# WL-CONTROL.net
KiCad netlist of a schematic drawn in Altium Designer
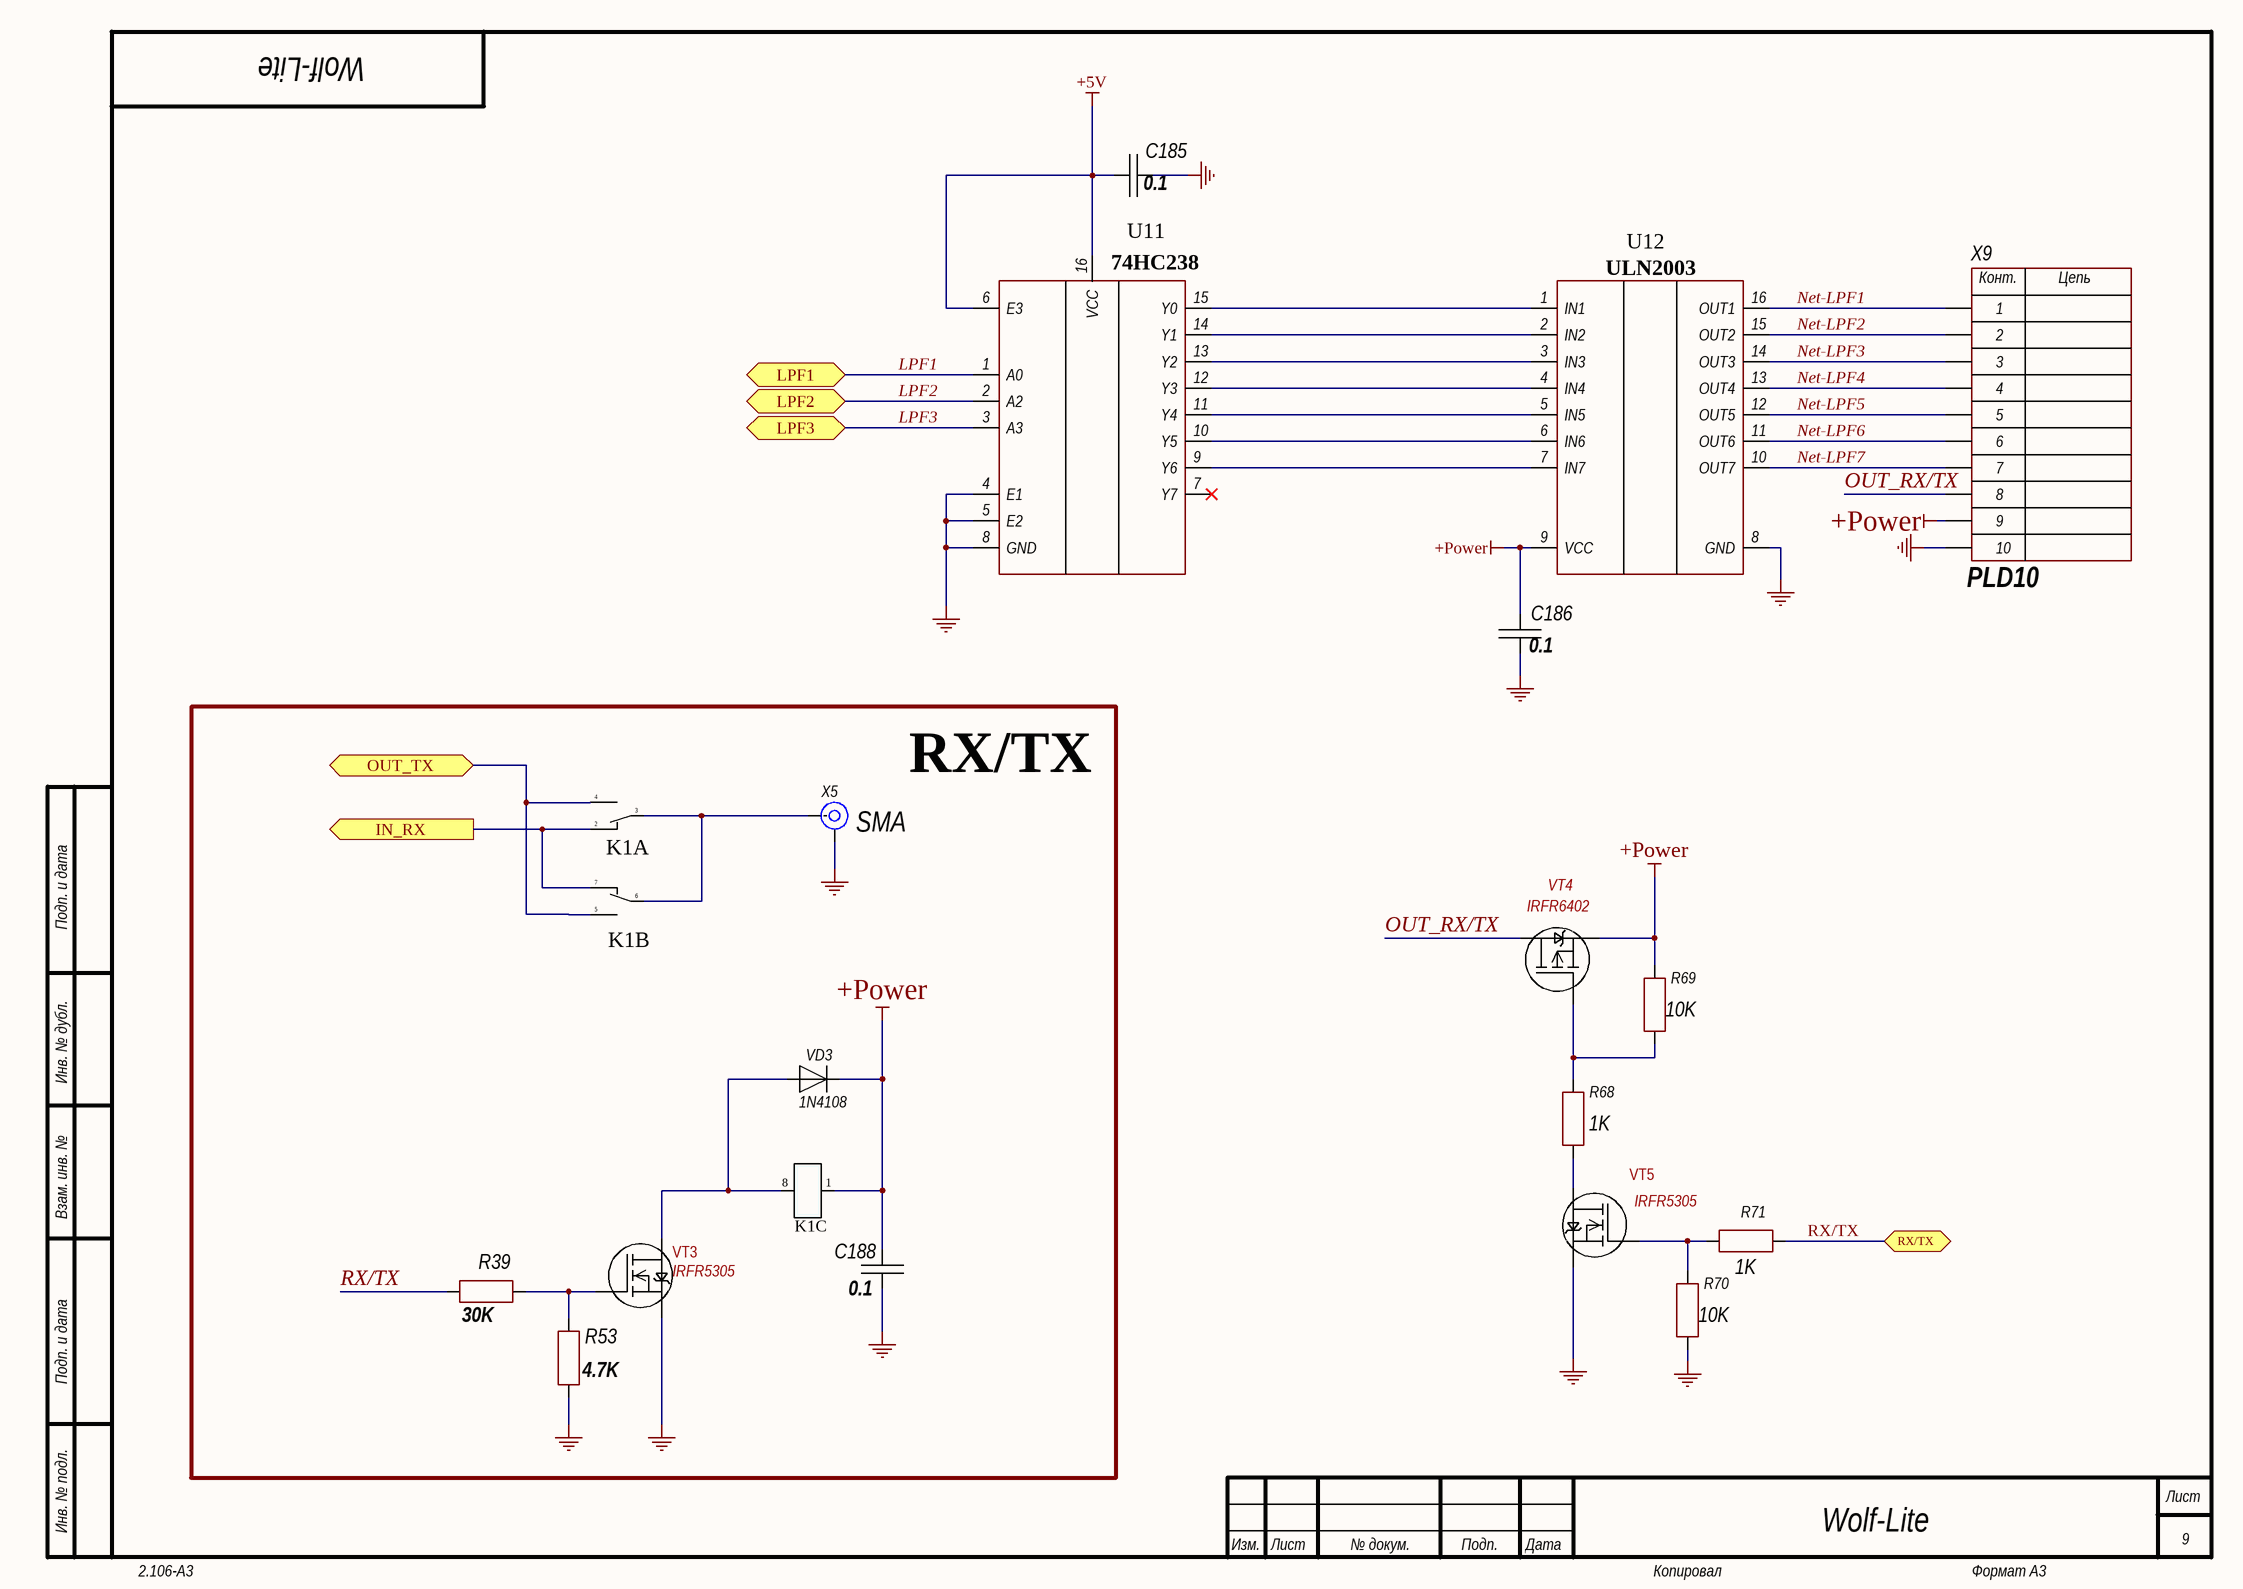
[diagram p0: WL-CONTROL.SchDoc]

(export (version "E")
  (design (tool "Eeschema 10.0.6"))
  (components
    (comp (ref "C185")
      (value "0.1")
      (footprint "standard:CH0805C")
      (libsource (lib "Discrete") (part "Capacitor"))
    )
    (comp (ref "C186")
      (value "0.1")
      (footprint "standard:CH0805C")
      (libsource (lib "Discrete") (part "Capacitor"))
    )
    (comp (ref "C188")
      (value "0.1")
      (footprint "standard:CH0805C")
      (libsource (lib "Discrete") (part "Capacitor"))
    )
    (comp (ref "K1") (value "IM06") (footprint "IMG06") (libsource (lib "Relay") (part "IM06-1")))
    (comp (ref "R39") (value "30K") (footprint "standard:CH0805R") (libsource (lib "") (part "Resistor_1")))
    (comp (ref "R53")
      (value "4.7K")
      (footprint "standard:CH0805R")
      (libsource (lib "Discrete") (part "Resistor"))
    )
    (comp (ref "R68")
      (value "1K")
      (footprint "standard:CH0805R")
      (libsource (lib "Discrete") (part "Resistor"))
    )
    (comp (ref "R69")
      (value "10K")
      (footprint "standard:CH0805R")
      (libsource (lib "Discrete") (part "Resistor"))
    )
    (comp (ref "R70")
      (value "10K")
      (footprint "standard:CH0805R")
      (libsource (lib "Discrete") (part "Resistor"))
    )
    (comp (ref "R71") (value "1K") (footprint "standard:CH0805R") (libsource (lib "") (part "Resistor_1")))
    (comp (ref "U11") (value "74HC238") (footprint "16-SOIC") (libsource (lib "Digital") (part "74HC238")))
    (comp (ref "U12")
      (value "ULN2003")
      (footprint "16-SOIC")
      (libsource (lib "Digital") (part "ULN2003_NEW"))
    )
    (comp (ref "VD3") (value "1N4108") (footprint "1N4148") (libsource (lib "Diods") (part "Diod")))
    (comp (ref "VT3") (value "IRFR5305") (footprint "SOT23_132") (libsource (lib "") (part "N-KANAL_1")))
    (comp (ref "VT4")
      (value "IRFR6402")
      (footprint "SOT23_132")
      (libsource (lib "Transistor") (part "P-KANAL"))
    )
    (comp (ref "VT5")
      (value "IRFR5305")
      (footprint "SOT23_132")
      (libsource (lib "Transistor") (part "N-KANAL"))
    )
    (comp (ref "X5")
      (value "SMA")
      (footprint "custom:CON: SMA")
      (description "RF")
      (libsource (lib "Connectors") (part "SMA"))
    )
    (comp (ref "X9")
      (value "PLD10")
      (footprint "custom:CON: PLD-10")
      (libsource (lib "Connectors") (part "10-Connector"))
    )
  )
  (nets
    (net (code "1") (name "+5V") (class "Default")
      (node (ref "C185") (pin "1") (pinfunction "1_1") (pintype "power_in"))
      (node (ref "U11") (pin "16") (pinfunction "VCC_16") (pintype "passive"))
      (node (ref "U11") (pin "6") (pinfunction "E3_6") (pintype "passive"))
    )
    (net (code "2") (name "+Power") (class "Default")
      (node (ref "C186") (pin "2") (pinfunction "2_2") (pintype "power_in"))
      (node (ref "C188") (pin "1") (pinfunction "1_1") (pintype "power_in"))
      (node (ref "K1") (pin "1") (pintype "passive"))
      (node (ref "R69") (pin "2") (pinfunction "2_2") (pintype "passive"))
      (node (ref "U12") (pin "9") (pinfunction "VCC_9") (pintype "passive"))
      (node (ref "VD3") (pin "2") (pinfunction "2_2") (pintype "passive"))
      (node (ref "VT4") (pin "2") (pinfunction "I_2") (pintype "passive"))
      (node (ref "X9") (pin "9") (pinfunction "9_9") (pintype "power_in"))
    )
    (net (code "3") (name "/IN_RX") (class "Default")
      (node (ref "K1") (pin "2") (pintype "passive"))
      (node (ref "K1") (pin "7") (pintype "passive"))
    )
    (net (code "4") (name "/LPF1") (class "Default")
      (node (ref "U11") (pin "1") (pinfunction "A0_1") (pintype "passive"))
    )
    (net (code "5") (name "/LPF2") (class "Default")
      (node (ref "U11") (pin "2") (pinfunction "A2_2") (pintype "passive"))
    )
    (net (code "6") (name "/LPF3") (class "Default")
      (node (ref "U11") (pin "3") (pinfunction "A3_3") (pintype "passive"))
    )
    (net (code "7") (name "/Net-LPF1") (class "Default")
      (node (ref "U12") (pin "16") (pinfunction "OUT1_16") (pintype "passive"))
      (node (ref "X9") (pin "1") (pinfunction "1_1") (pintype "passive"))
    )
    (net (code "8") (name "/Net-LPF2") (class "Default")
      (node (ref "U12") (pin "15") (pinfunction "OUT2_15") (pintype "passive"))
      (node (ref "X9") (pin "2") (pinfunction "2_2") (pintype "passive"))
    )
    (net (code "9") (name "/Net-LPF3") (class "Default")
      (node (ref "U12") (pin "14") (pinfunction "OUT3_14") (pintype "passive"))
      (node (ref "X9") (pin "3") (pinfunction "3_3") (pintype "power_in"))
    )
    (net (code "10") (name "/Net-LPF4") (class "Default")
      (node (ref "U12") (pin "13") (pinfunction "OUT4_13") (pintype "passive"))
      (node (ref "X9") (pin "4") (pinfunction "4_4") (pintype "power_in"))
    )
    (net (code "11") (name "/Net-LPF5") (class "Default")
      (node (ref "U12") (pin "12") (pinfunction "OUT5_12") (pintype "passive"))
      (node (ref "X9") (pin "5") (pinfunction "5_5") (pintype "power_in"))
    )
    (net (code "12") (name "/Net-LPF6") (class "Default")
      (node (ref "U12") (pin "11") (pinfunction "OUT6_11") (pintype "passive"))
      (node (ref "X9") (pin "6") (pinfunction "6_6") (pintype "power_in"))
    )
    (net (code "13") (name "/Net-LPF7") (class "Default")
      (node (ref "U12") (pin "10") (pinfunction "OUT7_10") (pintype "passive"))
      (node (ref "X9") (pin "7") (pinfunction "7_7") (pintype "power_in"))
    )
    (net (code "14") (name "/OUT_RX{slash}TX") (class "Default")
      (node (ref "VT4") (pin "3") (pinfunction "Сток(Drain)_3") (pintype "passive"))
      (node (ref "X9") (pin "8") (pinfunction "8_8") (pintype "power_in"))
    )
    (net (code "15") (name "/OUT_TX") (class "Default")
      (node (ref "K1") (pin "4") (pintype "passive"))
      (node (ref "K1") (pin "5") (pintype "passive"))
    )
    (net (code "16") (name "/RX{slash}TX") (class "Default")
      (node (ref "R39") (pin "2") (pinfunction "2_2") (pintype "passive"))
      (node (ref "R71") (pin "1") (pinfunction "1_1") (pintype "passive"))
    )
    (net (code "17") (name "GND") (class "Default")
      (node (ref "C185") (pin "2") (pinfunction "2_2") (pintype "power_in"))
      (node (ref "C186") (pin "1") (pinfunction "1_1") (pintype "power_in"))
      (node (ref "C188") (pin "2") (pinfunction "2_2") (pintype "power_in"))
      (node (ref "R53") (pin "1") (pinfunction "1_1") (pintype "passive"))
      (node (ref "R70") (pin "1") (pinfunction "1_1") (pintype "passive"))
      (node (ref "U11") (pin "4") (pinfunction "E1_4") (pintype "passive"))
      (node (ref "U11") (pin "5") (pinfunction "E2_5") (pintype "passive"))
      (node (ref "U11") (pin "8") (pinfunction "GND_8") (pintype "passive"))
      (node (ref "U12") (pin "8") (pinfunction "GND_8") (pintype "passive"))
      (node (ref "VT3") (pin "2") (pinfunction "I_2") (pintype "passive"))
      (node (ref "VT5") (pin "2") (pinfunction "I_2") (pintype "passive"))
      (node (ref "X5") (pin "2") (pinfunction "IN_2") (pintype "passive"))
      (node (ref "X9") (pin "10") (pinfunction "10_10") (pintype "power_in"))
    )
    (net (code "18") (name "Net-(K1-Pad3)") (class "Default")
      (node (ref "K1") (pin "3") (pintype "passive"))
      (node (ref "K1") (pin "6") (pintype "passive"))
      (node (ref "X5") (pin "1") (pinfunction "IN_1") (pintype "passive"))
    )
    (net (code "19") (name "Net-(U11-Y0)") (class "Default")
      (node (ref "U11") (pin "15") (pinfunction "Y0_15") (pintype "passive"))
      (node (ref "U12") (pin "1") (pinfunction "IN1_1") (pintype "passive"))
    )
    (net (code "20") (name "Net-(U11-Y1)") (class "Default")
      (node (ref "U11") (pin "14") (pinfunction "Y1_14") (pintype "passive"))
      (node (ref "U12") (pin "2") (pinfunction "IN2_2") (pintype "passive"))
    )
    (net (code "21") (name "Net-(U11-Y2)") (class "Default")
      (node (ref "U11") (pin "13") (pinfunction "Y2_13") (pintype "passive"))
      (node (ref "U12") (pin "3") (pinfunction "IN3_3") (pintype "passive"))
    )
    (net (code "22") (name "Net-(U11-Y3)") (class "Default")
      (node (ref "U11") (pin "12") (pinfunction "Y3_12") (pintype "passive"))
      (node (ref "U12") (pin "4") (pinfunction "IN4_4") (pintype "passive"))
    )
    (net (code "23") (name "Net-(U11-Y4)") (class "Default")
      (node (ref "U11") (pin "11") (pinfunction "Y4_11") (pintype "passive"))
      (node (ref "U12") (pin "5") (pinfunction "IN5_5") (pintype "passive"))
    )
    (net (code "24") (name "Net-(U11-Y5)") (class "Default")
      (node (ref "U11") (pin "10") (pinfunction "Y5_10") (pintype "passive"))
      (node (ref "U12") (pin "6") (pinfunction "IN6_6") (pintype "passive"))
    )
    (net (code "25") (name "Net-(U11-Y6)") (class "Default")
      (node (ref "U11") (pin "9") (pinfunction "Y6_9") (pintype "passive"))
      (node (ref "U12") (pin "7") (pinfunction "IN7_7") (pintype "passive"))
    )
    (net (code "26") (name "Net-(VT3-Затвор(Gate))") (class "Default")
      (node (ref "R39") (pin "1") (pinfunction "1_1") (pintype "passive"))
      (node (ref "R53") (pin "2") (pinfunction "2_2") (pintype "passive"))
      (node (ref "VT3") (pin "1") (pinfunction "Затвор(Gate)_1") (pintype "passive"))
    )
    (net (code "27") (name "Net-(VT3-Сток(Drain))") (class "Default")
      (node (ref "K1") (pin "8") (pintype "passive"))
      (node (ref "VD3") (pin "1") (pinfunction "1_1") (pintype "passive"))
      (node (ref "VT3") (pin "3") (pinfunction "Сток(Drain)_3") (pintype "passive"))
    )
    (net (code "28") (name "Net-(VT4-Затвор(Gate))") (class "Default")
      (node (ref "R68") (pin "2") (pinfunction "2_2") (pintype "passive"))
      (node (ref "R69") (pin "1") (pinfunction "1_1") (pintype "passive"))
      (node (ref "VT4") (pin "1") (pinfunction "Затвор(Gate)_1") (pintype "passive"))
    )
    (net (code "29") (name "Net-(VT5-Затвор(Gate))") (class "Default")
      (node (ref "R70") (pin "2") (pinfunction "2_2") (pintype "passive"))
      (node (ref "R71") (pin "2") (pinfunction "2_2") (pintype "passive"))
      (node (ref "VT5") (pin "1") (pinfunction "Затвор(Gate)_1") (pintype "passive"))
    )
    (net (code "30") (name "Net-(VT5-Сток(Drain))") (class "Default")
      (node (ref "R68") (pin "1") (pinfunction "1_1") (pintype "passive"))
      (node (ref "VT5") (pin "3") (pinfunction "Сток(Drain)_3") (pintype "passive"))
    )
    (net (code "31") (name "unconnected-(U11-Y7-Pad7)") (class "Default")
      (node (ref "U11") (pin "7") (pinfunction "Y7_7") (pintype "passive+no_connect"))
    )
  )
)
